# max-lader-1_3.net
KiCad netlist of a schematic drawn in EAGLE
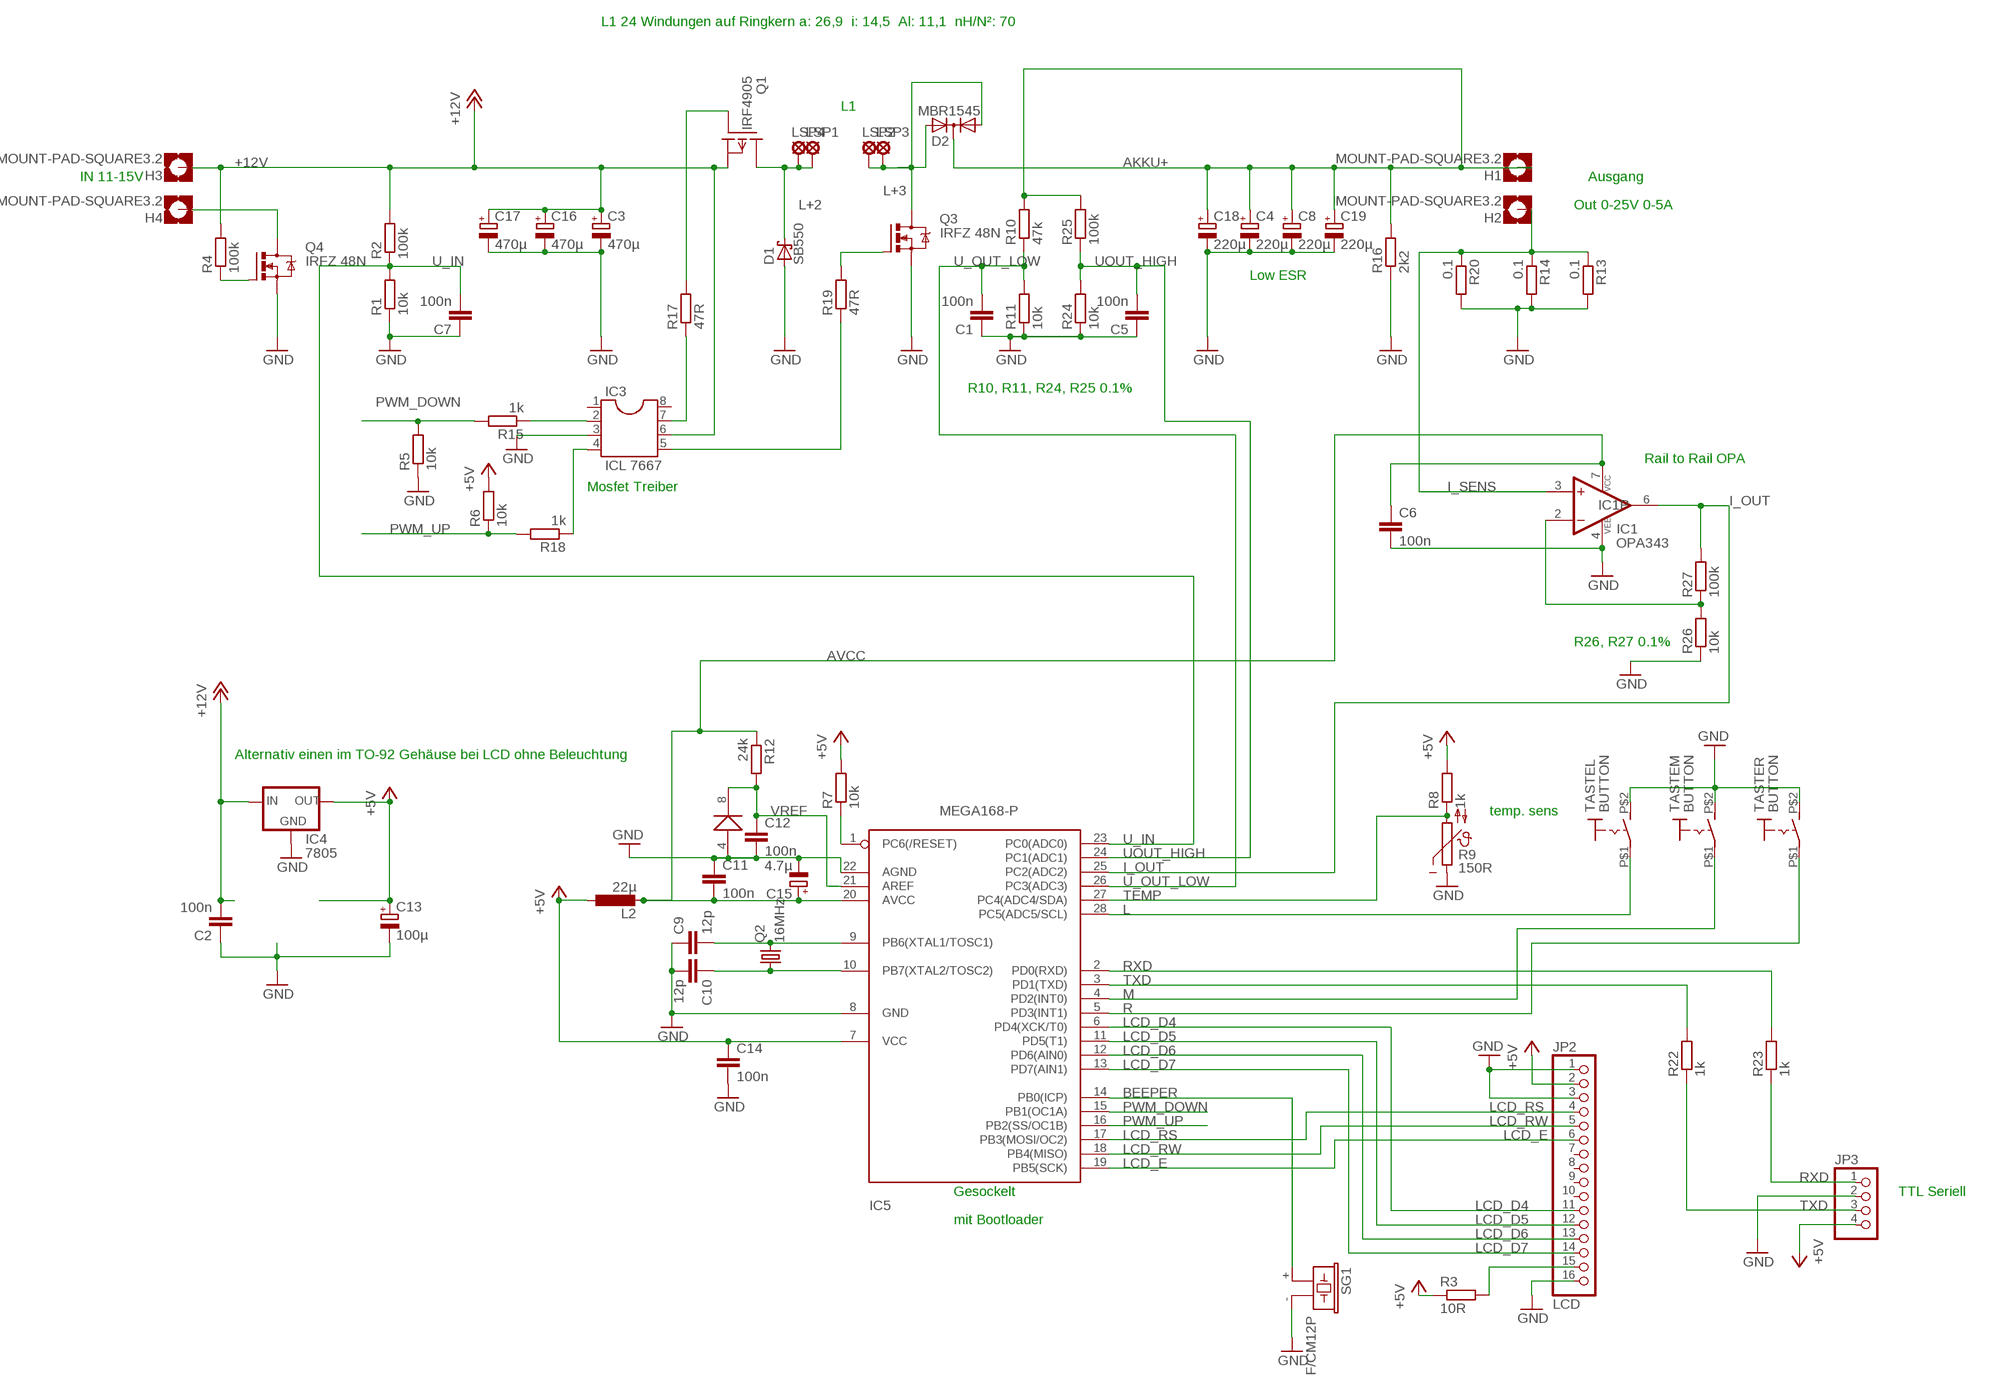
[diagram p0: schematic, sheet 1]

(export (version "E")
  (design (tool "Eeschema 10.0.6"))
  (components
    (comp (ref "C1")
      (value "100n")
      (footprint "eagle-import:C050-024X044")
      (libsource (lib "eagle-import") (part "C-EU050-024X044"))
    )
    (comp (ref "C2")
      (value "100n")
      (footprint "eagle-import:C050-025X075")
      (libsource (lib "eagle-import") (part "C-EU050-025X075"))
    )
    (comp (ref "C3")
      (value "470µ")
      (footprint "eagle-import:E3,5-8")
      (libsource (lib "eagle-import") (part "CPOL-EUE3.5-8"))
    )
    (comp (ref "C4")
      (value "220µ")
      (footprint "eagle-import:E3,5-8")
      (libsource (lib "eagle-import") (part "CPOL-EUE3.5-8"))
    )
    (comp (ref "C5")
      (value "100n")
      (footprint "eagle-import:C050-024X044")
      (libsource (lib "eagle-import") (part "C-EU050-024X044"))
    )
    (comp (ref "C6")
      (value "100n")
      (footprint "eagle-import:C050-024X044")
      (libsource (lib "eagle-import") (part "C-EU050-024X044"))
    )
    (comp (ref "C7")
      (value "100n")
      (footprint "eagle-import:C050-025X075")
      (libsource (lib "eagle-import") (part "C-EU050-025X075"))
    )
    (comp (ref "C8")
      (value "220µ")
      (footprint "eagle-import:E3,5-8")
      (libsource (lib "eagle-import") (part "CPOL-EUE3.5-8"))
    )
    (comp (ref "C9")
      (value "12p")
      (footprint "eagle-import:C050-024X044")
      (libsource (lib "eagle-import") (part "C-EU050-024X044"))
    )
    (comp (ref "C10")
      (value "12p")
      (footprint "eagle-import:C050-024X044")
      (libsource (lib "eagle-import") (part "C-EU050-024X044"))
    )
    (comp (ref "C11")
      (value "100n")
      (footprint "eagle-import:C050-025X075")
      (libsource (lib "eagle-import") (part "C-EU050-025X075"))
    )
    (comp (ref "C12")
      (value "100n")
      (footprint "eagle-import:C050-024X044")
      (libsource (lib "eagle-import") (part "C-EU050-024X044"))
    )
    (comp (ref "C13")
      (value "100µ")
      (footprint "eagle-import:E3,5-8")
      (libsource (lib "eagle-import") (part "CPOL-EUE3.5-8"))
    )
    (comp (ref "C14")
      (value "100n")
      (footprint "eagle-import:C050-024X044")
      (libsource (lib "eagle-import") (part "C-EU050-024X044"))
    )
    (comp (ref "C15")
      (value "4.7µ")
      (footprint "eagle-import:E2-4")
      (libsource (lib "eagle-import") (part "CPOL-EUE2-4"))
    )
    (comp (ref "C16")
      (value "470µ")
      (footprint "eagle-import:E3,5-8")
      (libsource (lib "eagle-import") (part "CPOL-EUE3.5-8"))
    )
    (comp (ref "C17")
      (value "470µ")
      (footprint "eagle-import:E3,5-8")
      (libsource (lib "eagle-import") (part "CPOL-EUE3.5-8"))
    )
    (comp (ref "C18")
      (value "220µ")
      (footprint "eagle-import:E3,5-8")
      (libsource (lib "eagle-import") (part "CPOL-EUE3.5-8"))
    )
    (comp (ref "C19")
      (value "220µ")
      (footprint "eagle-import:E3,5-8")
      (libsource (lib "eagle-import") (part "CPOL-EUE3.5-8"))
    )
    (comp (ref "D1")
      (value "SB550")
      (footprint "eagle-import:DO201T15")
      (libsource (lib "eagle-import") (part "SCHOTTKY-DIODEDO201T15"))
    )
    (comp (ref "D2")
      (value "MBR1545")
      (footprint "eagle-import:TO220ABS")
      (libsource (lib "eagle-import") (part "FEP16AT"))
    )
    (comp (ref "H1")
      (value "MOUNT-PAD-SQUARE3.2")
      (footprint "eagle-import:3,2-PAD-SQUARE")
      (libsource (lib "eagle-import") (part "MOUNT-PAD-SQUARE3.2"))
    )
    (comp (ref "H2")
      (value "MOUNT-PAD-SQUARE3.2")
      (footprint "eagle-import:3,2-PAD-SQUARE")
      (libsource (lib "eagle-import") (part "MOUNT-PAD-SQUARE3.2"))
    )
    (comp (ref "H3")
      (value "MOUNT-PAD-SQUARE3.2")
      (footprint "eagle-import:3,2-PAD-SQUARE")
      (libsource (lib "eagle-import") (part "MOUNT-PAD-SQUARE3.2"))
    )
    (comp (ref "H4")
      (value "MOUNT-PAD-SQUARE3.2")
      (footprint "eagle-import:3,2-PAD-SQUARE")
      (libsource (lib "eagle-import") (part "MOUNT-PAD-SQUARE3.2"))
    )
    (comp (ref "IC1")
      (value "OPA343")
      (footprint "eagle-import:SO08")
      (libsource (lib "eagle-import") (part "MAX4105ESA"))
    )
    (comp (ref "IC2")
      (value "LM385-2.5")
      (footprint "eagle-import:SO08")
      (libsource (lib "eagle-import") (part "LM385"))
    )
    (comp (ref "IC3")
      (value "ICL 7667")
      (footprint "eagle-import:DIL08")
      (libsource (lib "eagle-import") (part "DIL8"))
    )
    (comp (ref "IC4")
      (value "7805")
      (footprint "eagle-import:78XXL")
      (libsource (lib "eagle-import") (part "78XXL"))
    )
    (comp (ref "IC5")
      (value "MEGA168-P")
      (footprint "eagle-import:DIL28-3")
      (libsource (lib "eagle-import") (part "MEGA8-P"))
    )
    (comp (ref "JP2")
      (value "LCD")
      (footprint "eagle-import:1X16")
      (libsource (lib "eagle-import") (part "PINHD-1X16"))
    )
    (comp (ref "JP3")
      (value "PINHD-1X4")
      (footprint "eagle-import:1X04")
      (libsource (lib "eagle-import") (part "PINHD-1X4"))
    )
    (comp (ref "L2")
      (value "22µ")
      (footprint "eagle-import:0207_12")
      (libsource (lib "eagle-import") (part "L-EU0207/12"))
    )
    (comp (ref "LSP1")
      (value "SE13")
      (footprint "eagle-import:SE13")
      (libsource (lib "eagle-import") (part "SE13"))
    )
    (comp (ref "LSP2")
      (value "SE13")
      (footprint "eagle-import:SE13")
      (libsource (lib "eagle-import") (part "SE13"))
    )
    (comp (ref "LSP3")
      (value "SE13")
      (footprint "eagle-import:SE13")
      (libsource (lib "eagle-import") (part "SE13"))
    )
    (comp (ref "LSP4")
      (value "SE13")
      (footprint "eagle-import:SE13")
      (libsource (lib "eagle-import") (part "SE13"))
    )
    (comp (ref "Q1")
      (value "IRF4905")
      (footprint "eagle-import:TO220V")
      (libsource (lib "eagle-import") (part "IRF9530V"))
    )
    (comp (ref "Q2")
      (value "16MHz")
      (footprint "eagle-import:HC49_S")
      (libsource (lib "eagle-import") (part "CRYTALHC49S"))
    )
    (comp (ref "Q3")
      (value "IRFZ 48N")
      (footprint "eagle-import:TO220BV")
      (libsource (lib "eagle-import") (part "IRF740"))
    )
    (comp (ref "Q4")
      (value "IRFZ 48N")
      (footprint "eagle-import:TO220BV")
      (libsource (lib "eagle-import") (part "IRF740"))
    )
    (comp (ref "R1")
      (value "10k")
      (footprint "eagle-import:0207_10")
      (libsource (lib "eagle-import") (part "R-EU_0207/10"))
    )
    (comp (ref "R2")
      (value "100k")
      (footprint "eagle-import:0207_10")
      (libsource (lib "eagle-import") (part "R-EU_0207/10"))
    )
    (comp (ref "R3")
      (value "10R")
      (footprint "eagle-import:0207_10")
      (libsource (lib "eagle-import") (part "R-EU_0207/10"))
    )
    (comp (ref "R4")
      (value "100k")
      (footprint "eagle-import:0204_7")
      (libsource (lib "eagle-import") (part "R-EU_0204/7"))
    )
    (comp (ref "R5")
      (value "10k")
      (footprint "eagle-import:R0805")
      (libsource (lib "eagle-import") (part "R-EU_R0805"))
    )
    (comp (ref "R6")
      (value "10k")
      (footprint "eagle-import:R0805")
      (libsource (lib "eagle-import") (part "R-EU_R0805"))
    )
    (comp (ref "R7")
      (value "10k")
      (footprint "eagle-import:R0805")
      (libsource (lib "eagle-import") (part "R-EU_R0805"))
    )
    (comp (ref "R8")
      (value "1k")
      (footprint "eagle-import:R0805")
      (libsource (lib "eagle-import") (part "R-EU_R0805"))
    )
    (comp (ref "R9")
      (value "150R")
      (footprint "eagle-import:P642")
      (libsource (lib "eagle-import") (part "NTC642-6"))
    )
    (comp (ref "R10")
      (value "47k")
      (footprint "eagle-import:0207_10")
      (libsource (lib "eagle-import") (part "R-EU_0207/10"))
    )
    (comp (ref "R11")
      (value "10k")
      (footprint "eagle-import:0207_10")
      (libsource (lib "eagle-import") (part "R-EU_0207/10"))
    )
    (comp (ref "R12")
      (value "24k")
      (footprint "eagle-import:0207_10")
      (libsource (lib "eagle-import") (part "R-EU_0207/10"))
    )
    (comp (ref "R13")
      (value "0.1")
      (footprint "eagle-import:P0613_15")
      (libsource (lib "eagle-import") (part "R-EU_0613/15"))
    )
    (comp (ref "R14")
      (value "0.1")
      (footprint "eagle-import:P0613_15")
      (libsource (lib "eagle-import") (part "R-EU_0613/15"))
    )
    (comp (ref "R15")
      (value "1k")
      (footprint "eagle-import:R0805")
      (libsource (lib "eagle-import") (part "R-EU_R0805"))
    )
    (comp (ref "R16")
      (value "2k2")
      (footprint "eagle-import:0207_2V")
      (libsource (lib "eagle-import") (part "R-EU_0207/2V"))
    )
    (comp (ref "R17")
      (value "47R")
      (footprint "eagle-import:0207_10")
      (libsource (lib "eagle-import") (part "R-EU_0207/10"))
    )
    (comp (ref "R18")
      (value "1k")
      (footprint "eagle-import:R0805")
      (libsource (lib "eagle-import") (part "R-EU_R0805"))
    )
    (comp (ref "R19")
      (value "47R")
      (footprint "eagle-import:0207_10")
      (libsource (lib "eagle-import") (part "R-EU_0207/10"))
    )
    (comp (ref "R20")
      (value "0.1")
      (footprint "eagle-import:P0613_15")
      (libsource (lib "eagle-import") (part "R-EU_0613/15"))
    )
    (comp (ref "R22")
      (value "1k")
      (footprint "eagle-import:R0805")
      (libsource (lib "eagle-import") (part "R-EU_R0805"))
    )
    (comp (ref "R23")
      (value "1k")
      (footprint "eagle-import:R0805")
      (libsource (lib "eagle-import") (part "R-EU_R0805"))
    )
    (comp (ref "R24")
      (value "10k")
      (footprint "eagle-import:0207_10")
      (libsource (lib "eagle-import") (part "R-EU_0207/10"))
    )
    (comp (ref "R25")
      (value "100k")
      (footprint "eagle-import:0207_10")
      (libsource (lib "eagle-import") (part "R-EU_0207/10"))
    )
    (comp (ref "R26")
      (value "10k")
      (footprint "eagle-import:0207_10")
      (libsource (lib "eagle-import") (part "R-EU_0207/10"))
    )
    (comp (ref "R27")
      (value "100k")
      (footprint "eagle-import:0207_10")
      (libsource (lib "eagle-import") (part "R-EU_0207/10"))
    )
    (comp (ref "SG1")
      (value "F/CM12P")
      (footprint "eagle-import:F_CM12P")
      (libsource (lib "eagle-import") (part "F/CM12P"))
    )
    (comp (ref "TASTEL")
      (value "BUTTON")
      (footprint "eagle-import:BUT")
      (libsource (lib "eagle-import") (part "BUTTON"))
    )
    (comp (ref "TASTEM")
      (value "BUTTON")
      (footprint "eagle-import:BUT")
      (libsource (lib "eagle-import") (part "BUTTON"))
    )
    (comp (ref "TASTER")
      (value "BUTTON")
      (footprint "eagle-import:BUT")
      (libsource (lib "eagle-import") (part "BUTTON"))
    )
  )
  (nets
    (net (code "1") (name "+5V") (class "Default")
      (node (ref "C13") (pin "+") (pinfunction "+_+") (pintype "passive"))
      (node (ref "C14") (pin "1") (pinfunction "1_1") (pintype "passive"))
      (node (ref "IC4") (pin "OUT") (pinfunction "OUT_OUT") (pintype "passive"))
      (node (ref "IC5") (pin "7") (pinfunction "VCC_7") (pintype "bidirectional"))
      (node (ref "JP2") (pin "2") (pinfunction "2_2") (pintype "passive"))
      (node (ref "JP3") (pin "4") (pinfunction "4_4") (pintype "passive"))
      (node (ref "L2") (pin "1") (pinfunction "1_1") (pintype "passive"))
      (node (ref "R3") (pin "1") (pinfunction "1_1") (pintype "passive"))
      (node (ref "R6") (pin "2") (pinfunction "2_2") (pintype "passive"))
      (node (ref "R7") (pin "2") (pinfunction "2_2") (pintype "passive"))
      (node (ref "R8") (pin "2") (pinfunction "2_2") (pintype "passive"))
    )
    (net (code "2") (name "+12V") (class "Default")
      (node (ref "C16") (pin "+") (pinfunction "+_+") (pintype "passive"))
      (node (ref "C17") (pin "+") (pinfunction "+_+") (pintype "passive"))
      (node (ref "C2") (pin "2") (pinfunction "2_2") (pintype "passive"))
      (node (ref "C3") (pin "+") (pinfunction "+_+") (pintype "passive"))
      (node (ref "H3") (pin "B3,2") (pinfunction "MOUNT_B3,2") (pintype "passive"))
      (node (ref "IC3") (pin "6") (pinfunction "6_6") (pintype "passive"))
      (node (ref "IC4") (pin "IN") (pinfunction "IN_IN") (pintype "input"))
      (node (ref "Q1") (pin "3") (pinfunction "S_3") (pintype "passive"))
      (node (ref "R2") (pin "2") (pinfunction "2_2") (pintype "passive"))
      (node (ref "R4") (pin "2") (pinfunction "2_2") (pintype "passive"))
    )
    (net (code "3") (name "/AKKU+") (class "Default")
      (node (ref "C18") (pin "+") (pinfunction "+_+") (pintype "passive"))
      (node (ref "C19") (pin "+") (pinfunction "+_+") (pintype "passive"))
      (node (ref "C4") (pin "+") (pinfunction "+_+") (pintype "passive"))
      (node (ref "C8") (pin "+") (pinfunction "+_+") (pintype "passive"))
      (node (ref "D2") (pin "C") (pinfunction "C_C") (pintype "passive"))
      (node (ref "H1") (pin "B3,2") (pinfunction "MOUNT_B3,2") (pintype "passive"))
      (node (ref "R10") (pin "2") (pinfunction "2_2") (pintype "passive"))
      (node (ref "R16") (pin "2") (pinfunction "2_2") (pintype "passive"))
      (node (ref "R25") (pin "2") (pinfunction "2_2") (pintype "passive"))
    )
    (net (code "4") (name "/AVCC") (class "Default")
      (node (ref "C11") (pin "2") (pinfunction "2_2") (pintype "passive"))
      (node (ref "C15") (pin "+") (pinfunction "+_+") (pintype "passive"))
      (node (ref "C6") (pin "1") (pinfunction "1_1") (pintype "passive"))
      (node (ref "IC1") (pin "7") (pinfunction "VCC_7") (pintype "power_in"))
      (node (ref "IC5") (pin "20") (pinfunction "AVCC_20") (pintype "bidirectional"))
      (node (ref "L2") (pin "2") (pinfunction "2_2") (pintype "passive"))
      (node (ref "R12") (pin "1") (pinfunction "1_1") (pintype "passive"))
    )
    (net (code "5") (name "/BEEPER") (class "Default")
      (node (ref "IC5") (pin "14") (pinfunction "PB0(ICP)_14") (pintype "bidirectional"))
      (node (ref "SG1") (pin "+") (pinfunction "1_+") (pintype "passive"))
    )
    (net (code "6") (name "/I_OUT") (class "Default")
      (node (ref "IC1") (pin "6") (pinfunction "OUT_6") (pintype "output"))
      (node (ref "IC5") (pin "25") (pinfunction "PC2(ADC2)_25") (pintype "bidirectional"))
      (node (ref "R27") (pin "2") (pinfunction "2_2") (pintype "passive"))
    )
    (net (code "7") (name "/I_SENS") (class "Default")
      (node (ref "H2") (pin "B3,2") (pinfunction "MOUNT_B3,2") (pintype "passive"))
      (node (ref "IC1") (pin "3") (pinfunction "+IN_3") (pintype "input"))
      (node (ref "R13") (pin "1") (pinfunction "1_1") (pintype "passive"))
      (node (ref "R14") (pin "1") (pinfunction "1_1") (pintype "passive"))
      (node (ref "R20") (pin "1") (pinfunction "1_1") (pintype "passive"))
    )
    (net (code "8") (name "/L") (class "Default")
      (node (ref "IC5") (pin "28") (pinfunction "PC5(ADC5/SCL)_28") (pintype "bidirectional"))
      (node (ref "TASTEL") (pin "P$1") (pinfunction "P_P$1") (pintype "passive"))
    )
    (net (code "9") (name "/L+2") (class "Default")
      (node (ref "D1") (pin "C") (pinfunction "C_C") (pintype "passive"))
      (node (ref "LSP1") (pin "MP") (pinfunction "MP_MP") (pintype "passive"))
      (node (ref "LSP4") (pin "MP") (pinfunction "MP_MP") (pintype "passive"))
      (node (ref "Q1") (pin "2") (pinfunction "D_2") (pintype "passive"))
    )
    (net (code "10") (name "/L+3") (class "Default")
      (node (ref "D2") (pin "A1") (pinfunction "A1_A1") (pintype "passive"))
      (node (ref "D2") (pin "A2") (pinfunction "A2_A2") (pintype "passive"))
      (node (ref "LSP2") (pin "MP") (pinfunction "MP_MP") (pintype "passive"))
      (node (ref "LSP3") (pin "MP") (pinfunction "MP_MP") (pintype "passive"))
      (node (ref "Q3") (pin "D") (pinfunction "D_D") (pintype "passive"))
    )
    (net (code "11") (name "/LCD_D4") (class "Default")
      (node (ref "IC5") (pin "6") (pinfunction "PD4(XCK/T0)_6") (pintype "bidirectional"))
      (node (ref "JP2") (pin "11") (pinfunction "11_11") (pintype "passive"))
    )
    (net (code "12") (name "/LCD_D5") (class "Default")
      (node (ref "IC5") (pin "11") (pinfunction "PD5(T1)_11") (pintype "bidirectional"))
      (node (ref "JP2") (pin "12") (pinfunction "12_12") (pintype "passive"))
    )
    (net (code "13") (name "/LCD_D6") (class "Default")
      (node (ref "IC5") (pin "12") (pinfunction "PD6(AIN0)_12") (pintype "bidirectional"))
      (node (ref "JP2") (pin "13") (pinfunction "13_13") (pintype "passive"))
    )
    (net (code "14") (name "/LCD_D7") (class "Default")
      (node (ref "IC5") (pin "13") (pinfunction "PD7(AIN1)_13") (pintype "bidirectional"))
      (node (ref "JP2") (pin "14") (pinfunction "14_14") (pintype "passive"))
    )
    (net (code "15") (name "/LCD_E") (class "Default")
      (node (ref "IC5") (pin "19") (pinfunction "PB5(SCK)_19") (pintype "bidirectional"))
      (node (ref "JP2") (pin "6") (pinfunction "6_6") (pintype "passive"))
    )
    (net (code "16") (name "/LCD_RS") (class "Default")
      (node (ref "IC5") (pin "17") (pinfunction "PB3(MOSI/OC2)_17") (pintype "bidirectional"))
      (node (ref "JP2") (pin "4") (pinfunction "4_4") (pintype "passive"))
    )
    (net (code "17") (name "/LCD_RW") (class "Default")
      (node (ref "IC5") (pin "18") (pinfunction "PB4(MISO)_18") (pintype "bidirectional"))
      (node (ref "JP2") (pin "5") (pinfunction "5_5") (pintype "passive"))
    )
    (net (code "18") (name "/M") (class "Default")
      (node (ref "IC5") (pin "4") (pinfunction "PD2(INT0)_4") (pintype "bidirectional"))
      (node (ref "TASTEM") (pin "P$1") (pinfunction "P_P$1") (pintype "passive"))
    )
    (net (code "19") (name "/PWM_DOWN") (class "Default")
      (node (ref "IC5") (pin "15") (pinfunction "PB1(OC1A)_15") (pintype "bidirectional"))
      (node (ref "R15") (pin "2") (pinfunction "2_2") (pintype "passive"))
      (node (ref "R5") (pin "2") (pinfunction "2_2") (pintype "passive"))
    )
    (net (code "20") (name "/PWM_UP") (class "Default")
      (node (ref "IC5") (pin "16") (pinfunction "PB2(SS/OC1B)_16") (pintype "bidirectional"))
      (node (ref "R18") (pin "2") (pinfunction "2_2") (pintype "passive"))
      (node (ref "R6") (pin "1") (pinfunction "1_1") (pintype "passive"))
    )
    (net (code "21") (name "/R") (class "Default")
      (node (ref "IC5") (pin "5") (pinfunction "PD3(INT1)_5") (pintype "bidirectional"))
      (node (ref "TASTER") (pin "P$1") (pinfunction "P_P$1") (pintype "passive"))
    )
    (net (code "22") (name "/RXD") (class "Default")
      (node (ref "IC5") (pin "2") (pinfunction "PD0(RXD)_2") (pintype "bidirectional"))
      (node (ref "R23") (pin "2") (pinfunction "2_2") (pintype "passive"))
    )
    (net (code "23") (name "/TEMP") (class "Default")
      (node (ref "IC5") (pin "27") (pinfunction "PC4(ADC4/SDA)_27") (pintype "bidirectional"))
      (node (ref "R8") (pin "1") (pinfunction "1_1") (pintype "passive"))
      (node (ref "R9") (pin "2") (pinfunction "2_2") (pintype "passive"))
    )
    (net (code "24") (name "/TXD") (class "Default")
      (node (ref "IC5") (pin "3") (pinfunction "PD1(TXD)_3") (pintype "bidirectional"))
      (node (ref "R22") (pin "2") (pinfunction "2_2") (pintype "passive"))
    )
    (net (code "25") (name "/UOUT_HIGH") (class "Default")
      (node (ref "C5") (pin "2") (pinfunction "2_2") (pintype "passive"))
      (node (ref "IC5") (pin "24") (pinfunction "PC1(ADC1)_24") (pintype "bidirectional"))
      (node (ref "R24") (pin "2") (pinfunction "2_2") (pintype "passive"))
      (node (ref "R25") (pin "1") (pinfunction "1_1") (pintype "passive"))
    )
    (net (code "26") (name "/U_IN") (class "Default")
      (node (ref "C7") (pin "2") (pinfunction "2_2") (pintype "passive"))
      (node (ref "IC5") (pin "23") (pinfunction "PC0(ADC0)_23") (pintype "bidirectional"))
      (node (ref "R1") (pin "2") (pinfunction "2_2") (pintype "passive"))
      (node (ref "R2") (pin "1") (pinfunction "1_1") (pintype "passive"))
    )
    (net (code "27") (name "/U_OUT_LOW") (class "Default")
      (node (ref "C1") (pin "2") (pinfunction "2_2") (pintype "passive"))
      (node (ref "IC5") (pin "26") (pinfunction "PC3(ADC3)_26") (pintype "bidirectional"))
      (node (ref "R10") (pin "1") (pinfunction "1_1") (pintype "passive"))
      (node (ref "R11") (pin "2") (pinfunction "2_2") (pintype "passive"))
    )
    (net (code "28") (name "/VREF") (class "Default")
      (node (ref "C12") (pin "1") (pinfunction "1_1") (pintype "passive"))
      (node (ref "IC2") (pin "8") (pinfunction "CATODE_8") (pintype "bidirectional"))
      (node (ref "IC5") (pin "21") (pinfunction "AREF_21") (pintype "bidirectional"))
      (node (ref "R12") (pin "2") (pinfunction "2_2") (pintype "passive"))
    )
    (net (code "29") (name "GND") (class "Default")
      (node (ref "C1") (pin "1") (pinfunction "1_1") (pintype "passive"))
      (node (ref "C10") (pin "2") (pinfunction "2_2") (pintype "passive"))
      (node (ref "C11") (pin "1") (pinfunction "1_1") (pintype "passive"))
      (node (ref "C12") (pin "2") (pinfunction "2_2") (pintype "passive"))
      (node (ref "C13") (pin "-") (pinfunction "-_-") (pintype "passive"))
      (node (ref "C14") (pin "2") (pinfunction "2_2") (pintype "passive"))
      (node (ref "C15") (pin "-") (pinfunction "-_-") (pintype "passive"))
      (node (ref "C16") (pin "-") (pinfunction "-_-") (pintype "passive"))
      (node (ref "C17") (pin "-") (pinfunction "-_-") (pintype "passive"))
      (node (ref "C18") (pin "-") (pinfunction "-_-") (pintype "passive"))
      (node (ref "C19") (pin "-") (pinfunction "-_-") (pintype "passive"))
      (node (ref "C2") (pin "1") (pinfunction "1_1") (pintype "passive"))
      (node (ref "C3") (pin "-") (pinfunction "-_-") (pintype "passive"))
      (node (ref "C4") (pin "-") (pinfunction "-_-") (pintype "passive"))
      (node (ref "C5") (pin "1") (pinfunction "1_1") (pintype "passive"))
      (node (ref "C6") (pin "2") (pinfunction "2_2") (pintype "passive"))
      (node (ref "C7") (pin "1") (pinfunction "1_1") (pintype "passive"))
      (node (ref "C8") (pin "-") (pinfunction "-_-") (pintype "passive"))
      (node (ref "C9") (pin "1") (pinfunction "1_1") (pintype "passive"))
      (node (ref "D1") (pin "A") (pinfunction "A_A") (pintype "passive"))
      (node (ref "IC1") (pin "4") (pinfunction "VEE_4") (pintype "power_in"))
      (node (ref "IC2") (pin "4") (pinfunction "ANODE_4") (pintype "bidirectional"))
      (node (ref "IC3") (pin "3") (pinfunction "3_3") (pintype "passive"))
      (node (ref "IC4") (pin "GND") (pinfunction "GND_GND") (pintype "input"))
      (node (ref "IC5") (pin "22") (pinfunction "AGND_22") (pintype "bidirectional"))
      (node (ref "IC5") (pin "8") (pinfunction "GND_8") (pintype "bidirectional"))
      (node (ref "JP2") (pin "1") (pinfunction "1_1") (pintype "passive"))
      (node (ref "JP2") (pin "16") (pinfunction "16_16") (pintype "passive"))
      (node (ref "JP2") (pin "3") (pinfunction "3_3") (pintype "passive"))
      (node (ref "JP3") (pin "2") (pinfunction "2_2") (pintype "passive"))
      (node (ref "Q3") (pin "S") (pinfunction "S_S") (pintype "passive"))
      (node (ref "Q4") (pin "S") (pinfunction "S_S") (pintype "passive"))
      (node (ref "R1") (pin "1") (pinfunction "1_1") (pintype "passive"))
      (node (ref "R11") (pin "1") (pinfunction "1_1") (pintype "passive"))
      (node (ref "R13") (pin "2") (pinfunction "2_2") (pintype "passive"))
      (node (ref "R14") (pin "2") (pinfunction "2_2") (pintype "passive"))
      (node (ref "R16") (pin "1") (pinfunction "1_1") (pintype "passive"))
      (node (ref "R20") (pin "2") (pinfunction "2_2") (pintype "passive"))
      (node (ref "R24") (pin "1") (pinfunction "1_1") (pintype "passive"))
      (node (ref "R26") (pin "1") (pinfunction "1_1") (pintype "passive"))
      (node (ref "R5") (pin "1") (pinfunction "1_1") (pintype "passive"))
      (node (ref "R9") (pin "1") (pinfunction "1_1") (pintype "passive"))
      (node (ref "SG1") (pin "-") (pinfunction "2_-") (pintype "passive"))
      (node (ref "TASTEL") (pin "P$2") (pinfunction "S_P$2") (pintype "passive"))
      (node (ref "TASTEM") (pin "P$2") (pinfunction "S_P$2") (pintype "passive"))
      (node (ref "TASTER") (pin "P$2") (pinfunction "S_P$2") (pintype "passive"))
    )
    (net (code "30") (name "Net-(H4-MOUNT)") (class "Default")
      (node (ref "H4") (pin "B3,2") (pinfunction "MOUNT_B3,2") (pintype "passive"))
      (node (ref "Q4") (pin "D") (pinfunction "D_D") (pintype "passive"))
    )
    (net (code "31") (name "Net-(IC1A--IN)") (class "Default")
      (node (ref "IC1") (pin "2") (pinfunction "-IN_2") (pintype "input"))
      (node (ref "R26") (pin "2") (pinfunction "2_2") (pintype "passive"))
      (node (ref "R27") (pin "1") (pinfunction "1_1") (pintype "passive"))
    )
    (net (code "32") (name "Net-(IC3-Pad2)") (class "Default")
      (node (ref "IC3") (pin "2") (pinfunction "2_2") (pintype "passive"))
      (node (ref "R15") (pin "1") (pinfunction "1_1") (pintype "passive"))
    )
    (net (code "33") (name "Net-(IC3-Pad4)") (class "Default")
      (node (ref "IC3") (pin "4") (pinfunction "4_4") (pintype "passive"))
      (node (ref "R18") (pin "1") (pinfunction "1_1") (pintype "passive"))
    )
    (net (code "34") (name "Net-(IC3-Pad5)") (class "Default")
      (node (ref "IC3") (pin "5") (pinfunction "5_5") (pintype "passive"))
      (node (ref "R19") (pin "1") (pinfunction "1_1") (pintype "passive"))
    )
    (net (code "35") (name "Net-(IC3-Pad7)") (class "Default")
      (node (ref "IC3") (pin "7") (pinfunction "7_7") (pintype "passive"))
      (node (ref "R17") (pin "1") (pinfunction "1_1") (pintype "passive"))
    )
    (net (code "36") (name "Net-(IC5-PB6(XTAL1{slash}TOSC1))") (class "Default")
      (node (ref "C9") (pin "2") (pinfunction "2_2") (pintype "passive"))
      (node (ref "IC5") (pin "9") (pinfunction "PB6(XTAL1/TOSC1)_9") (pintype "bidirectional"))
      (node (ref "Q2") (pin "2") (pinfunction "2_2") (pintype "passive"))
    )
    (net (code "37") (name "Net-(IC5-PB7(XTAL2{slash}TOSC2))") (class "Default")
      (node (ref "C10") (pin "1") (pinfunction "1_1") (pintype "passive"))
      (node (ref "IC5") (pin "10") (pinfunction "PB7(XTAL2/TOSC2)_10") (pintype "bidirectional"))
      (node (ref "Q2") (pin "1") (pinfunction "1_1") (pintype "passive"))
    )
    (net (code "38") (name "Net-(IC5-PC6({slash}RESET))") (class "Default")
      (node (ref "IC5") (pin "1") (pinfunction "PC6(/RESET)_1") (pintype "bidirectional"))
      (node (ref "R7") (pin "1") (pinfunction "1_1") (pintype "passive"))
    )
    (net (code "39") (name "Net-(JP2-Pad15)") (class "Default")
      (node (ref "JP2") (pin "15") (pinfunction "15_15") (pintype "passive"))
      (node (ref "R3") (pin "2") (pinfunction "2_2") (pintype "passive"))
    )
    (net (code "40") (name "Net-(JP3-Pad1)") (class "Default")
      (node (ref "JP3") (pin "1") (pinfunction "1_1") (pintype "passive"))
      (node (ref "R23") (pin "1") (pinfunction "1_1") (pintype "passive"))
    )
    (net (code "41") (name "Net-(JP3-Pad3)") (class "Default")
      (node (ref "JP3") (pin "3") (pinfunction "3_3") (pintype "passive"))
      (node (ref "R22") (pin "1") (pinfunction "1_1") (pintype "passive"))
    )
    (net (code "42") (name "Net-(Q1-G)") (class "Default")
      (node (ref "Q1") (pin "1") (pinfunction "G_1") (pintype "passive"))
      (node (ref "R17") (pin "2") (pinfunction "2_2") (pintype "passive"))
    )
    (net (code "43") (name "Net-(Q3-PadG)") (class "Default")
      (node (ref "Q3") (pin "G") (pinfunction "G_G") (pintype "passive"))
      (node (ref "R19") (pin "2") (pinfunction "2_2") (pintype "passive"))
    )
    (net (code "44") (name "Net-(Q4-PadG)") (class "Default")
      (node (ref "Q4") (pin "G") (pinfunction "G_G") (pintype "passive"))
      (node (ref "R4") (pin "1") (pinfunction "1_1") (pintype "passive"))
    )
    (net (code "45") (name "unconnected-(IC3-Pad1)") (class "Default")
      (node (ref "IC3") (pin "1") (pinfunction "1_1") (pintype "passive"))
    )
    (net (code "46") (name "unconnected-(IC3-Pad8)") (class "Default")
      (node (ref "IC3") (pin "8") (pinfunction "8_8") (pintype "passive"))
    )
    (net (code "47") (name "unconnected-(JP2-Pad7)") (class "Default")
      (node (ref "JP2") (pin "7") (pinfunction "7_7") (pintype "passive"))
    )
    (net (code "48") (name "unconnected-(JP2-Pad8)") (class "Default")
      (node (ref "JP2") (pin "8") (pinfunction "8_8") (pintype "passive"))
    )
    (net (code "49") (name "unconnected-(JP2-Pad9)") (class "Default")
      (node (ref "JP2") (pin "9") (pinfunction "9_9") (pintype "passive"))
    )
    (net (code "50") (name "unconnected-(JP2-Pad10)") (class "Default")
      (node (ref "JP2") (pin "10") (pinfunction "10_10") (pintype "passive"))
    )
  )
)
